# PocketBeagle.net
KiCad netlist of a schematic drawn in EAGLE
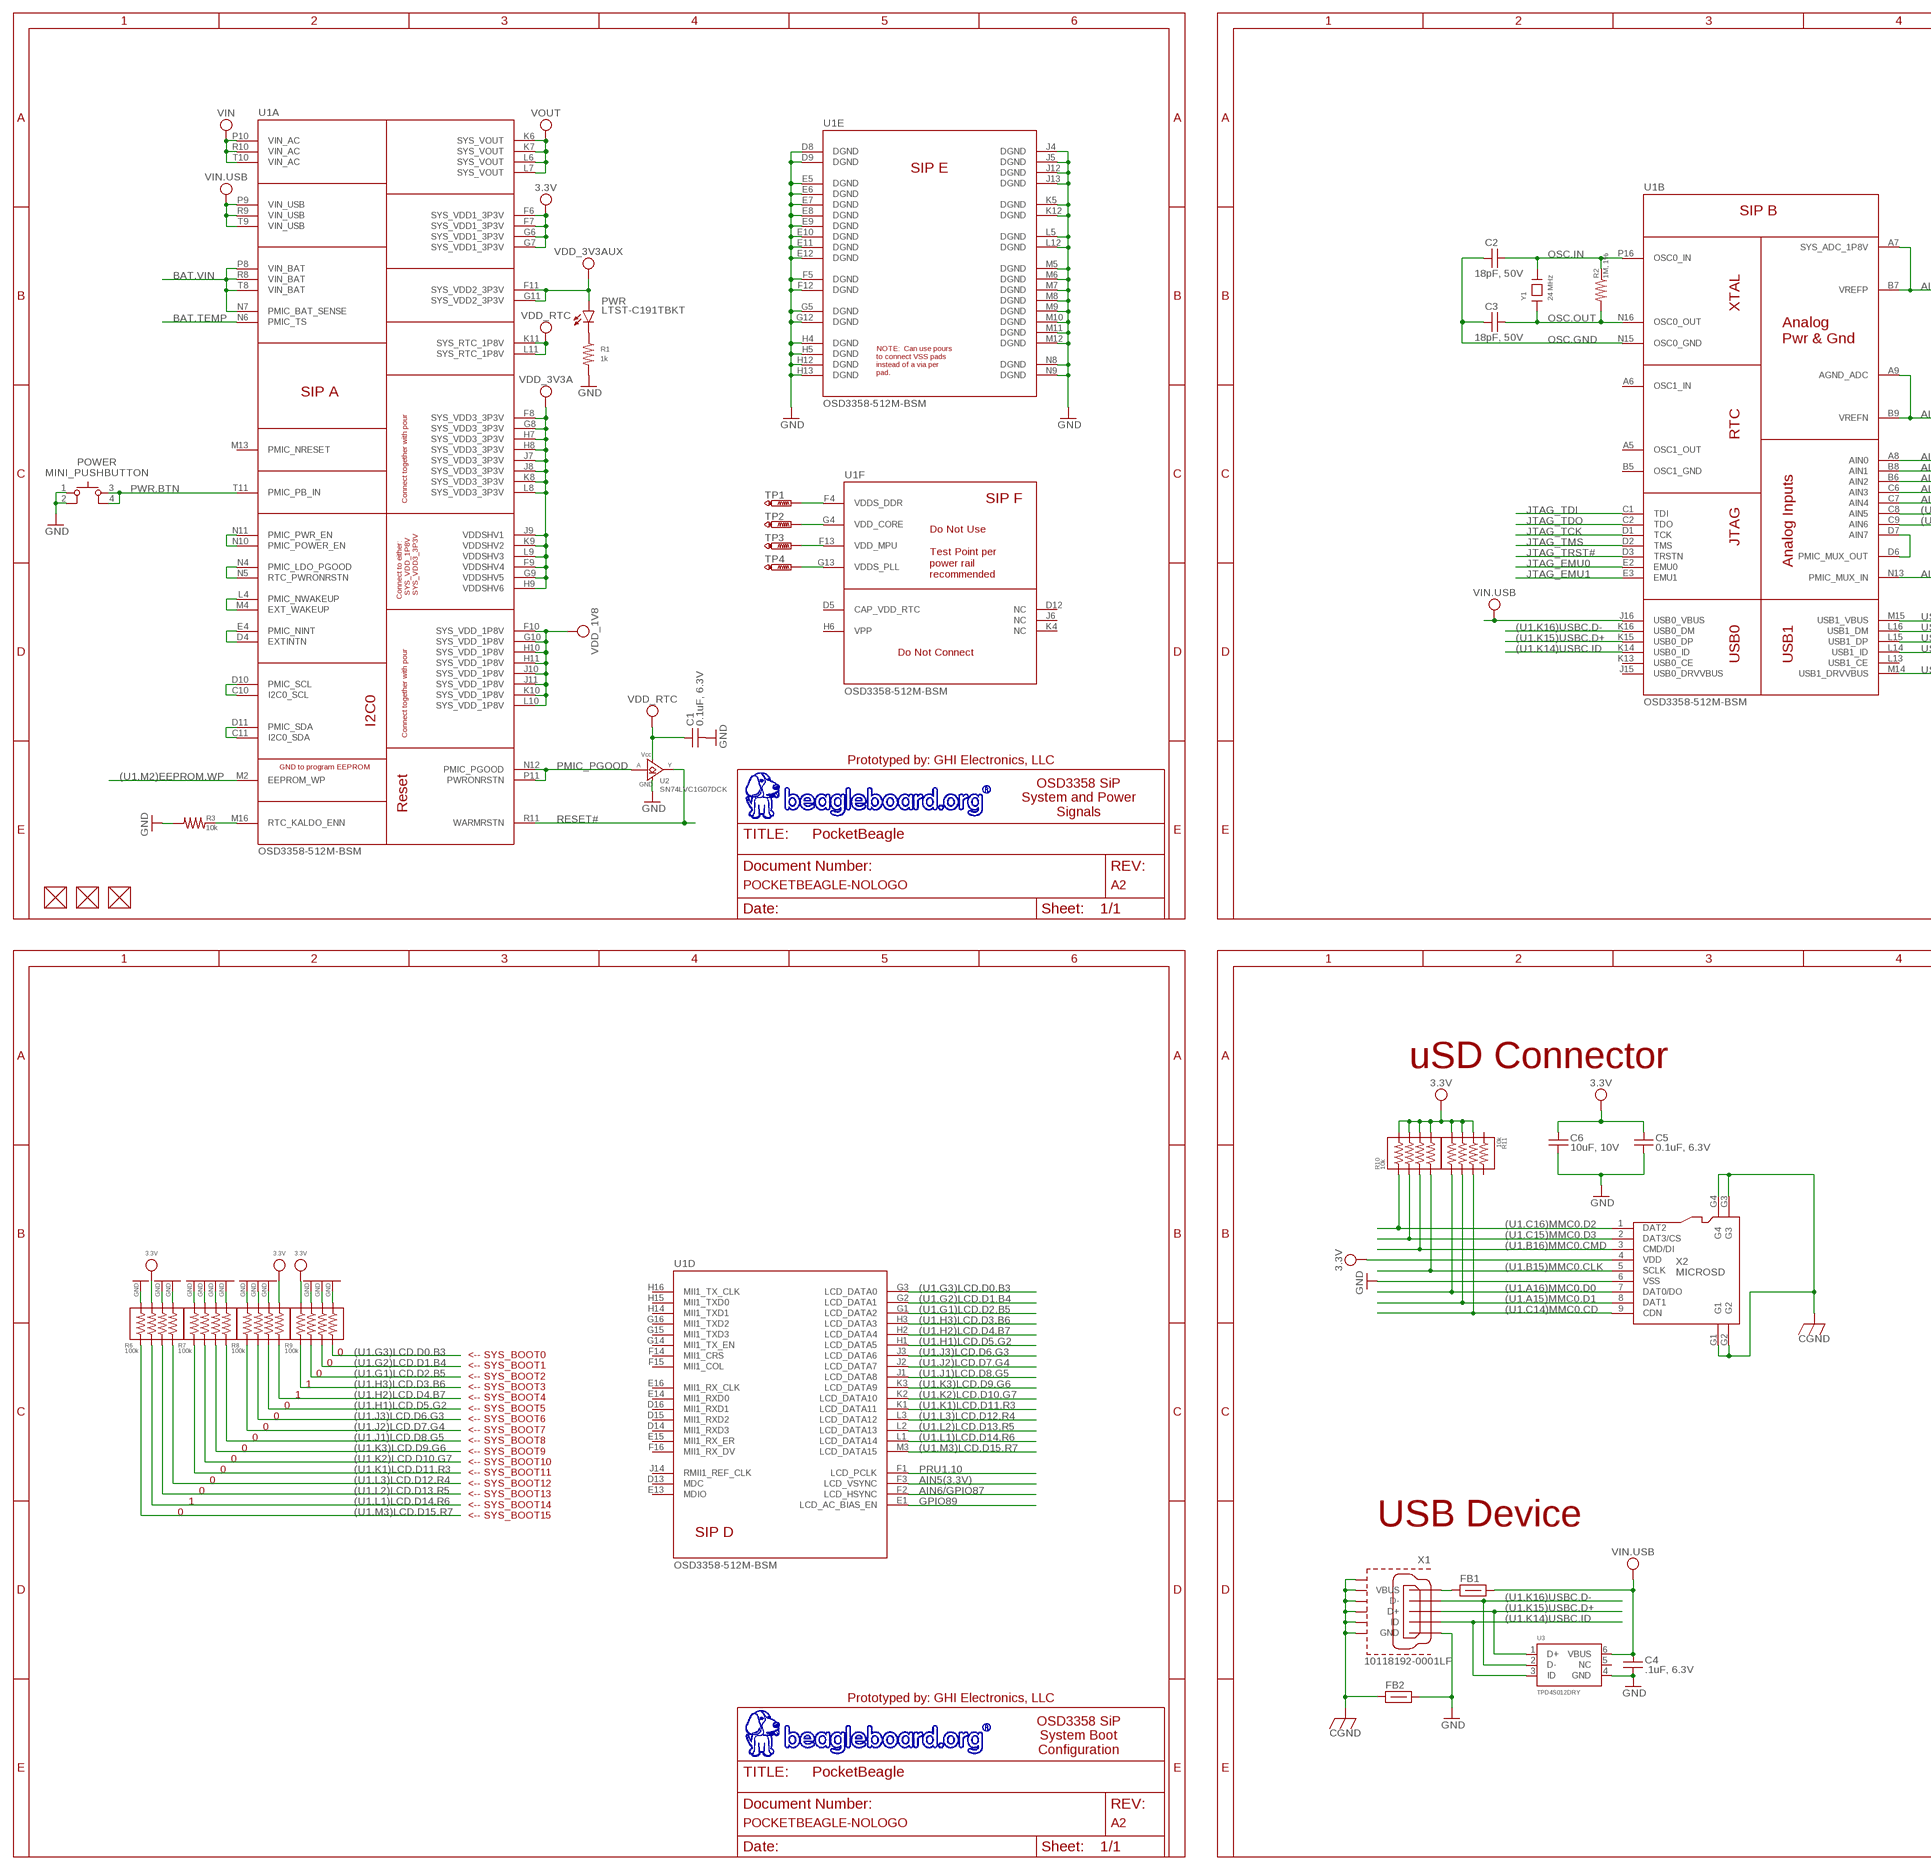
[diagram p0: schematic, sheet 1, part 1 of 2]
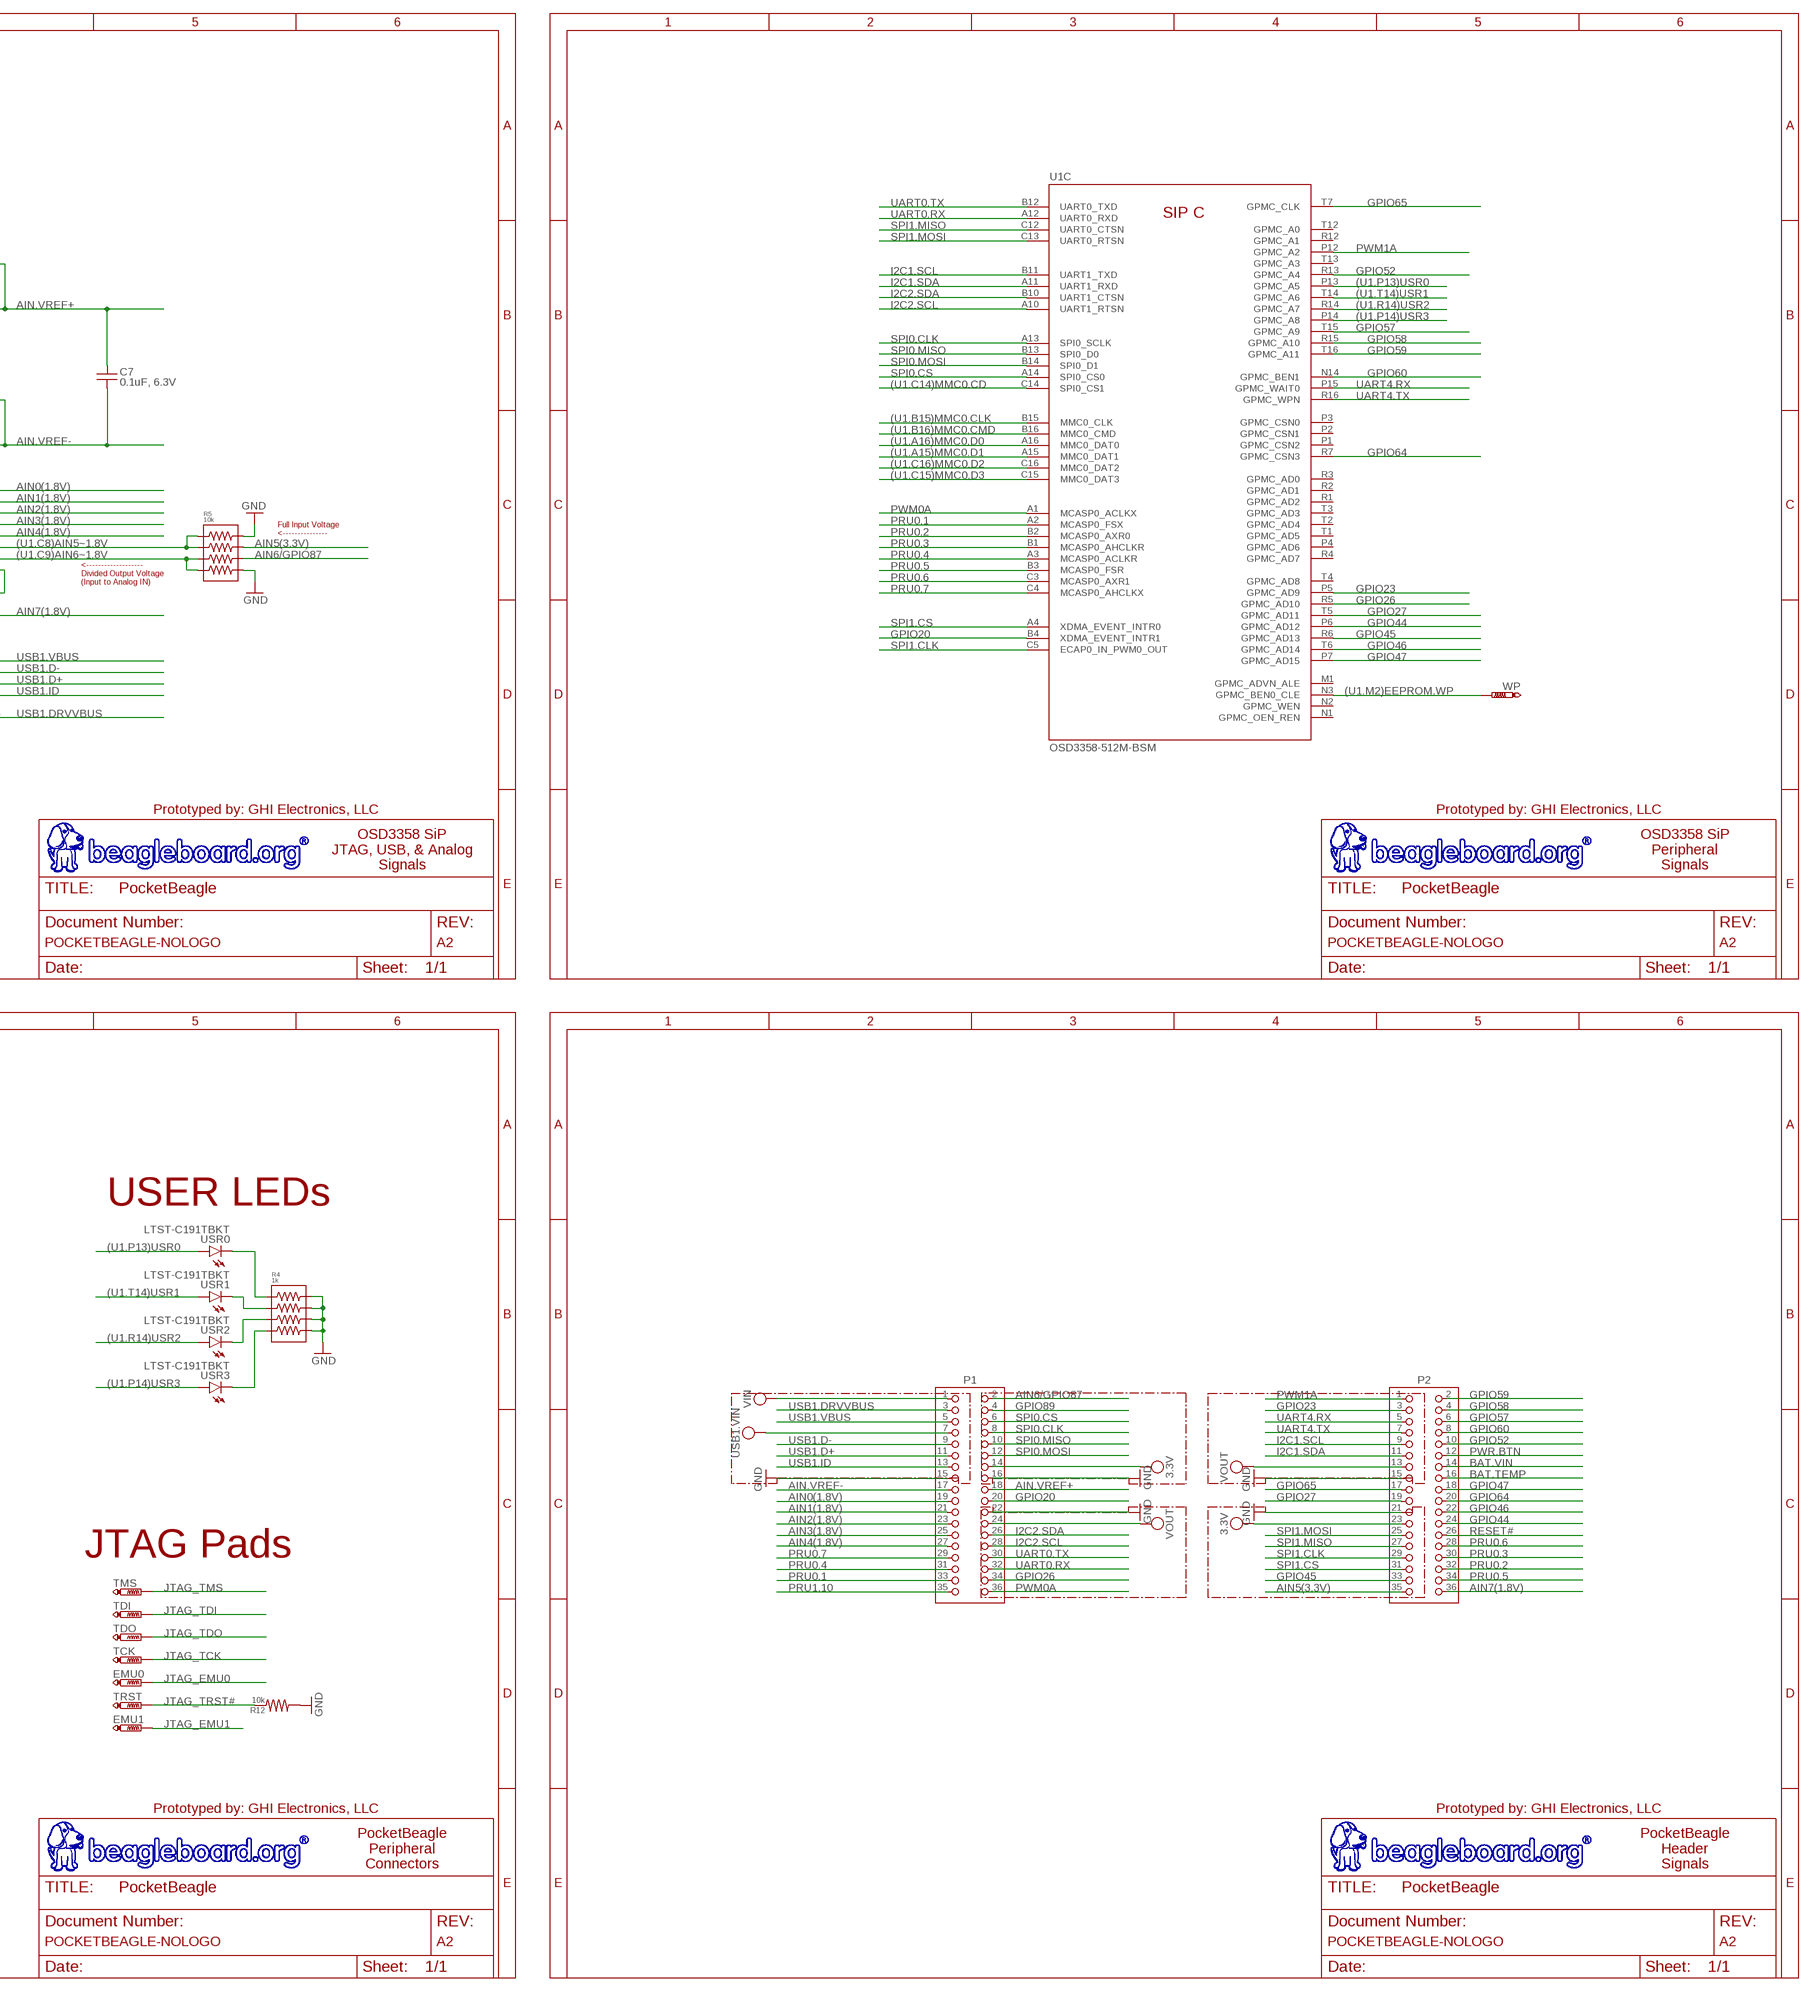
[diagram p1: schematic, sheet 1, part 2 of 2]

(export (version "E")
  (design (tool "Eeschema 10.0.6"))
  (components
    (comp (ref "C1")
      (value "0.1uF, 6.3V")
      (footprint "eagle-import:0402")
      (libsource (lib "eagle-import") (part "CAPACITOR-(INCH)-0402"))
    )
    (comp (ref "C2")
      (value "18pF, 50V")
      (footprint "eagle-import:0402")
      (libsource (lib "eagle-import") (part "CAPACITOR-(INCH)-0402"))
    )
    (comp (ref "C3")
      (value "18pF, 50V")
      (footprint "eagle-import:0402")
      (libsource (lib "eagle-import") (part "CAPACITOR-(INCH)-0402"))
    )
    (comp (ref "C4")
      (value ".1uF, 6.3V")
      (footprint "eagle-import:0402")
      (libsource (lib "eagle-import") (part "CAPACITOR-(INCH)-0402"))
    )
    (comp (ref "C5")
      (value "0.1uF, 6.3V")
      (footprint "eagle-import:0402")
      (libsource (lib "eagle-import") (part "CAPACITOR-(INCH)-0402"))
    )
    (comp (ref "C6")
      (value "10uF, 10V")
      (footprint "eagle-import:0603")
      (libsource (lib "eagle-import") (part "CAPACITOR-(INCH)-0603"))
    )
    (comp (ref "C7")
      (value "0.1uF, 6.3V")
      (footprint "eagle-import:0402")
      (libsource (lib "eagle-import") (part "CAPACITOR-(INCH)-0402"))
    )
    (comp (ref "EMU0")
      (value "PTR1B1,27")
      (footprint "eagle-import:B1,27")
      (libsource (lib "eagle-import") (part "PTR1B1,27"))
    )
    (comp (ref "EMU1")
      (value "PTR1B1,27")
      (footprint "eagle-import:B1,27")
      (libsource (lib "eagle-import") (part "PTR1B1,27"))
    )
    (comp (ref "FB1")
      (value "FB-(INCH)-0603")
      (footprint "eagle-import:0603")
      (libsource (lib "eagle-import") (part "FB-(INCH)-0603"))
    )
    (comp (ref "FB2")
      (value "FB-(INCH)-0603")
      (footprint "eagle-import:0603")
      (libsource (lib "eagle-import") (part "FB-(INCH)-0603"))
    )
    (comp (ref "FUD1")
      (value "FIDUCIAL")
      (footprint "eagle-import:FIDUCIAL_40MIL")
      (libsource (lib "eagle-import") (part "FIDUCIAL"))
    )
    (comp (ref "FUD2")
      (value "FIDUCIAL")
      (footprint "eagle-import:FIDUCIAL_40MIL")
      (libsource (lib "eagle-import") (part "FIDUCIAL"))
    )
    (comp (ref "FUD3")
      (value "FIDUCIAL")
      (footprint "eagle-import:FIDUCIAL_40MIL")
      (libsource (lib "eagle-import") (part "FIDUCIAL"))
    )
    (comp (ref "P1")
      (value "2X18-(INCH)-0.1-TH-(35MIL-DIA)-W/O-SILK")
      (footprint "eagle-import:TH-2X18-(35MIL-DIA)-W_O-SILK")
      (libsource (lib "eagle-import") (part "2X18-(INCH)-0.1-TH-(35MIL-DIA)-W/O-SILK"))
    )
    (comp (ref "P2")
      (value "2X18-(INCH)-0.1-TH-(35MIL-DIA)-W/O-SILK")
      (footprint "eagle-import:TH-2X18-(35MIL-DIA)-W_O-SILK")
      (libsource (lib "eagle-import") (part "2X18-(INCH)-0.1-TH-(35MIL-DIA)-W/O-SILK"))
    )
    (comp (ref "POWER")
      (value "MINI_PUSHBUTTON")
      (footprint "eagle-import:MINI_PUSHBUTTON")
      (libsource (lib "eagle-import") (part "MINI_PUSHBUTTON"))
    )
    (comp (ref "PWR")
      (value "LTST-C191TBKT")
      (footprint "eagle-import:0603-LED")
      (libsource (lib "eagle-import") (part "LED-(INCH)-0603"))
    )
    (comp (ref "R1")
      (value "1k")
      (footprint "eagle-import:0402")
      (libsource (lib "eagle-import") (part "RESISTOR-(INCH)-0402"))
    )
    (comp (ref "R2")
      (value "1M, 1%")
      (footprint "eagle-import:0402")
      (libsource (lib "eagle-import") (part "RESISTOR-(INCH)-0402"))
    )
    (comp (ref "R3")
      (value "10k")
      (footprint "eagle-import:0402")
      (libsource (lib "eagle-import") (part "RESISTOR-(INCH)-0402"))
    )
    (comp (ref "R4")
      (value "1k")
      (footprint "eagle-import:RN0804")
      (libsource (lib "eagle-import") (part "RESISTOR.NETWORK-(4)"))
    )
    (comp (ref "R5")
      (value "10k")
      (footprint "eagle-import:RN0804")
      (libsource (lib "eagle-import") (part "RESISTOR.NETWORK-(4)"))
    )
    (comp (ref "R6")
      (value "100k")
      (footprint "eagle-import:RN0804")
      (libsource (lib "eagle-import") (part "RESISTOR.NETWORK-(4)"))
    )
    (comp (ref "R7")
      (value "100k")
      (footprint "eagle-import:RN0804")
      (libsource (lib "eagle-import") (part "RESISTOR.NETWORK-(4)"))
    )
    (comp (ref "R8")
      (value "100k")
      (footprint "eagle-import:RN0804")
      (libsource (lib "eagle-import") (part "RESISTOR.NETWORK-(4)"))
    )
    (comp (ref "R9")
      (value "100k")
      (footprint "eagle-import:RN0804")
      (libsource (lib "eagle-import") (part "RESISTOR.NETWORK-(4)"))
    )
    (comp (ref "R10")
      (value "10k")
      (footprint "eagle-import:RN0804")
      (libsource (lib "eagle-import") (part "RESISTOR.NETWORK-(4)"))
    )
    (comp (ref "R11")
      (value "10k")
      (footprint "eagle-import:RN0804")
      (libsource (lib "eagle-import") (part "RESISTOR.NETWORK-(4)"))
    )
    (comp (ref "R12")
      (value "10k")
      (footprint "eagle-import:0402")
      (libsource (lib "eagle-import") (part "RESISTOR-(INCH)-0402"))
    )
    (comp (ref "TCK")
      (value "PTR1B1,27")
      (footprint "eagle-import:B1,27")
      (libsource (lib "eagle-import") (part "PTR1B1,27"))
    )
    (comp (ref "TDI")
      (value "PTR1B1,27")
      (footprint "eagle-import:B1,27")
      (libsource (lib "eagle-import") (part "PTR1B1,27"))
    )
    (comp (ref "TDO")
      (value "PTR1B1,27")
      (footprint "eagle-import:B1,27")
      (libsource (lib "eagle-import") (part "PTR1B1,27"))
    )
    (comp (ref "TMS")
      (value "PTR1B1,27")
      (footprint "eagle-import:B1,27")
      (libsource (lib "eagle-import") (part "PTR1B1,27"))
    )
    (comp (ref "TP1")
      (value "PTR1B1,27")
      (footprint "eagle-import:B1,27")
      (libsource (lib "eagle-import") (part "PTR1B1,27"))
    )
    (comp (ref "TP2")
      (value "PTR1B1,27")
      (footprint "eagle-import:B1,27")
      (libsource (lib "eagle-import") (part "PTR1B1,27"))
    )
    (comp (ref "TP3")
      (value "PTR1B1,27")
      (footprint "eagle-import:B1,27")
      (libsource (lib "eagle-import") (part "PTR1B1,27"))
    )
    (comp (ref "TP4")
      (value "PTR1B1,27")
      (footprint "eagle-import:B1,27")
      (libsource (lib "eagle-import") (part "PTR1B1,27"))
    )
    (comp (ref "TRST")
      (value "PTR1B1,27")
      (footprint "eagle-import:B1,27")
      (libsource (lib "eagle-import") (part "PTR1B1,27"))
    )
    (comp (ref "U1")
      (value "OSD3358-512M-BSM")
      (footprint "eagle-import:OSD335X-BGA-256")
      (libsource (lib "eagle-import") (part "OSD3358-512M-BSM"))
    )
    (comp (ref "U2")
      (value "SN74LVC1G07DCK")
      (footprint "eagle-import:SC70(TI-DCK)")
      (libsource (lib "eagle-import") (part "SN74LVC1G07DCK"))
    )
    (comp (ref "U3")
      (value "TPD4S012DRY")
      (footprint "eagle-import:SON-6(TI)-DRY")
      (libsource (lib "eagle-import") (part "TPD4S012DRYR"))
    )
    (comp (ref "USR0")
      (value "LTST-C191TBKT")
      (footprint "eagle-import:0603-LED")
      (libsource (lib "eagle-import") (part "LED-(INCH)-0603"))
    )
    (comp (ref "USR1")
      (value "LTST-C191TBKT")
      (footprint "eagle-import:0603-LED")
      (libsource (lib "eagle-import") (part "LED-(INCH)-0603"))
    )
    (comp (ref "USR2")
      (value "LTST-C191TBKT")
      (footprint "eagle-import:0603-LED")
      (libsource (lib "eagle-import") (part "LED-(INCH)-0603"))
    )
    (comp (ref "USR3")
      (value "LTST-C191TBKT")
      (footprint "eagle-import:0603-LED")
      (libsource (lib "eagle-import") (part "LED-(INCH)-0603"))
    )
    (comp (ref "WP")
      (value "PTR1B1,27")
      (footprint "eagle-import:B1,27")
      (libsource (lib "eagle-import") (part "PTR1B1,27"))
    )
    (comp (ref "X1")
      (value "10118192-0001LF")
      (footprint "eagle-import:10118192-0001LF(MICRO-USB-B-AMPHENOL-FCI)")
      (libsource (lib "eagle-import") (part "10118192-0001LF"))
    )
    (comp (ref "X2")
      (value "MICROSD")
      (footprint "eagle-import:MICROSD")
      (libsource (lib "eagle-import") (part "MICROSD"))
    )
    (comp (ref "Y1")
      (value "24 MHz")
      (footprint "eagle-import:CRYSTAL_5X3.2MM")
      (libsource (lib "eagle-import") (part "CRYSTAL_5X3.2MM"))
    )
  )
  (nets
    (net (code "1") (name "/(U1.A15)MMC0.D1") (class "Default")
      (node (ref "R11") (pin "6") (pinfunction "6_6") (pintype "bidirectional"))
      (node (ref "U1") (pin "A15") (pinfunction "MMC0_DAT1_A15") (pintype "bidirectional"))
      (node (ref "X2") (pin "8") (pinfunction "DAT1_8") (pintype "bidirectional"))
    )
    (net (code "2") (name "/(U1.A16)MMC0.D0") (class "Default")
      (node (ref "R11") (pin "5") (pinfunction "5_5") (pintype "bidirectional"))
      (node (ref "U1") (pin "A16") (pinfunction "MMC0_DAT0_A16") (pintype "bidirectional"))
      (node (ref "X2") (pin "7") (pinfunction "DAT0/DO_7") (pintype "bidirectional"))
    )
    (net (code "3") (name "/(U1.B15)MMC0.CLK") (class "Default")
      (node (ref "R10") (pin "4") (pinfunction "4_4") (pintype "bidirectional"))
      (node (ref "U1") (pin "B15") (pinfunction "MMC0_CLK_B15") (pintype "bidirectional"))
      (node (ref "X2") (pin "5") (pinfunction "SCLK_5") (pintype "bidirectional"))
    )
    (net (code "4") (name "/(U1.B16)MMC0.CMD") (class "Default")
      (node (ref "R10") (pin "3") (pinfunction "3_3") (pintype "bidirectional"))
      (node (ref "U1") (pin "B16") (pinfunction "MMC0_CMD_B16") (pintype "bidirectional"))
      (node (ref "X2") (pin "3") (pinfunction "CMD/DI_3") (pintype "bidirectional"))
    )
    (net (code "5") (name "/(U1.C8)AIN5~{1.8V}") (class "Default")
      (node (ref "R5") (pin "1") (pinfunction "1_1") (pintype "bidirectional"))
      (node (ref "R5") (pin "2") (pinfunction "2_2") (pintype "bidirectional"))
      (node (ref "U1") (pin "C8") (pinfunction "AIN5_C8") (pintype "bidirectional"))
    )
    (net (code "6") (name "/(U1.C9)AIN6~{1.8V}") (class "Default")
      (node (ref "R5") (pin "3") (pinfunction "3_3") (pintype "bidirectional"))
      (node (ref "R5") (pin "4") (pinfunction "4_4") (pintype "bidirectional"))
      (node (ref "U1") (pin "C9") (pinfunction "AIN6_C9") (pintype "bidirectional"))
    )
    (net (code "7") (name "/(U1.C14)MMC0.CD") (class "Default")
      (node (ref "R11") (pin "7") (pinfunction "7_7") (pintype "bidirectional"))
      (node (ref "U1") (pin "C14") (pinfunction "SPI0_CS1_C14") (pintype "bidirectional"))
      (node (ref "X2") (pin "9") (pinfunction "CDN_9") (pintype "bidirectional"))
    )
    (net (code "8") (name "/(U1.C15)MMC0.D3") (class "Default")
      (node (ref "R10") (pin "2") (pinfunction "2_2") (pintype "bidirectional"))
      (node (ref "U1") (pin "C15") (pinfunction "MMC0_DAT3_C15") (pintype "bidirectional"))
      (node (ref "X2") (pin "2") (pinfunction "DAT3/CS_2") (pintype "bidirectional"))
    )
    (net (code "9") (name "/(U1.C16)MMC0.D2") (class "Default")
      (node (ref "R10") (pin "1") (pinfunction "1_1") (pintype "bidirectional"))
      (node (ref "U1") (pin "C16") (pinfunction "MMC0_DAT2_C16") (pintype "bidirectional"))
      (node (ref "X2") (pin "1") (pinfunction "DAT2_1") (pintype "bidirectional"))
    )
    (net (code "10") (name "/(U1.G1)LCD.D2.B5") (class "Default")
      (node (ref "R9") (pin "6") (pinfunction "6_6") (pintype "bidirectional"))
      (node (ref "U1") (pin "G1") (pinfunction "LCD_DATA2_G1") (pintype "bidirectional"))
    )
    (net (code "11") (name "/(U1.G2)LCD.D1.B4") (class "Default")
      (node (ref "R9") (pin "7") (pinfunction "7_7") (pintype "bidirectional"))
      (node (ref "U1") (pin "G2") (pinfunction "LCD_DATA1_G2") (pintype "bidirectional"))
    )
    (net (code "12") (name "/(U1.G3)LCD.D0.B3") (class "Default")
      (node (ref "R9") (pin "8") (pinfunction "8_8") (pintype "bidirectional"))
      (node (ref "U1") (pin "G3") (pinfunction "LCD_DATA0_G3") (pintype "bidirectional"))
    )
    (net (code "13") (name "/(U1.H1)LCD.D5.G2") (class "Default")
      (node (ref "R8") (pin "3") (pinfunction "3_3") (pintype "bidirectional"))
      (node (ref "U1") (pin "H1") (pinfunction "LCD_DATA5_H1") (pintype "bidirectional"))
    )
    (net (code "14") (name "/(U1.H2)LCD.D4.B7") (class "Default")
      (node (ref "R8") (pin "4") (pinfunction "4_4") (pintype "bidirectional"))
      (node (ref "U1") (pin "H2") (pinfunction "LCD_DATA4_H2") (pintype "bidirectional"))
    )
    (net (code "15") (name "/(U1.H3)LCD.D3.B6") (class "Default")
      (node (ref "R9") (pin "5") (pinfunction "5_5") (pintype "bidirectional"))
      (node (ref "U1") (pin "H3") (pinfunction "LCD_DATA3_H3") (pintype "bidirectional"))
    )
    (net (code "16") (name "/(U1.J1)LCD.D8.G5") (class "Default")
      (node (ref "R7") (pin "4") (pinfunction "4_4") (pintype "bidirectional"))
      (node (ref "U1") (pin "J1") (pinfunction "LCD_DATA8_J1") (pintype "bidirectional"))
    )
    (net (code "17") (name "/(U1.J2)LCD.D7.G4") (class "Default")
      (node (ref "R8") (pin "1") (pinfunction "1_1") (pintype "bidirectional"))
      (node (ref "U1") (pin "J2") (pinfunction "LCD_DATA7_J2") (pintype "bidirectional"))
    )
    (net (code "18") (name "/(U1.J3)LCD.D6.G3") (class "Default")
      (node (ref "R8") (pin "2") (pinfunction "2_2") (pintype "bidirectional"))
      (node (ref "U1") (pin "J3") (pinfunction "LCD_DATA6_J3") (pintype "bidirectional"))
    )
    (net (code "19") (name "/(U1.K1)LCD.D11.R3") (class "Default")
      (node (ref "R7") (pin "1") (pinfunction "1_1") (pintype "bidirectional"))
      (node (ref "U1") (pin "K1") (pinfunction "LCD_DATA11_K1") (pintype "bidirectional"))
    )
    (net (code "20") (name "/(U1.K2)LCD.D10.G7") (class "Default")
      (node (ref "R7") (pin "2") (pinfunction "2_2") (pintype "bidirectional"))
      (node (ref "U1") (pin "K2") (pinfunction "LCD_DATA10_K2") (pintype "bidirectional"))
    )
    (net (code "21") (name "/(U1.K3)LCD.D9.G6") (class "Default")
      (node (ref "R7") (pin "3") (pinfunction "3_3") (pintype "bidirectional"))
      (node (ref "U1") (pin "K3") (pinfunction "LCD_DATA9_K3") (pintype "bidirectional"))
    )
    (net (code "22") (name "/(U1.K14)USBC.ID") (class "Default")
      (node (ref "U1") (pin "K14") (pinfunction "USB0_ID_K14") (pintype "bidirectional"))
      (node (ref "U3") (pin "3") (pinfunction "ID_3") (pintype "bidirectional"))
      (node (ref "X1") (pin "ID") (pinfunction "ID_ID") (pintype "input"))
    )
    (net (code "23") (name "/(U1.K15)USBC.D+") (class "Default")
      (node (ref "U1") (pin "K15") (pinfunction "USB0_DP_K15") (pintype "bidirectional"))
      (node (ref "U3") (pin "1") (pinfunction "D+_1") (pintype "bidirectional"))
      (node (ref "X1") (pin "D+") (pinfunction "D+_D+") (pintype "input"))
    )
    (net (code "24") (name "/(U1.K16)USBC.D-") (class "Default")
      (node (ref "U1") (pin "K16") (pinfunction "USB0_DM_K16") (pintype "bidirectional"))
      (node (ref "U3") (pin "2") (pinfunction "D-_2") (pintype "bidirectional"))
      (node (ref "X1") (pin "D-") (pinfunction "D-_D-") (pintype "input"))
    )
    (net (code "25") (name "/(U1.L1)LCD.D14.R6") (class "Default")
      (node (ref "R6") (pin "2") (pinfunction "2_2") (pintype "bidirectional"))
      (node (ref "U1") (pin "L1") (pinfunction "LCD_DATA14_L1") (pintype "bidirectional"))
    )
    (net (code "26") (name "/(U1.L2)LCD.D13.R5") (class "Default")
      (node (ref "R6") (pin "3") (pinfunction "3_3") (pintype "bidirectional"))
      (node (ref "U1") (pin "L2") (pinfunction "LCD_DATA13_L2") (pintype "bidirectional"))
    )
    (net (code "27") (name "/(U1.L3)LCD.D12.R4") (class "Default")
      (node (ref "R6") (pin "4") (pinfunction "4_4") (pintype "bidirectional"))
      (node (ref "U1") (pin "L3") (pinfunction "LCD_DATA12_L3") (pintype "bidirectional"))
    )
    (net (code "28") (name "/(U1.M2)EEPROM.WP") (class "Default")
      (node (ref "U1") (pin "M2") (pinfunction "EEPROM_WP_M2") (pintype "bidirectional"))
      (node (ref "U1") (pin "N3") (pinfunction "GPMC_BEN0_CLE_N3") (pintype "bidirectional"))
      (node (ref "WP") (pin "TP") (pinfunction "TP_TP") (pintype "input"))
    )
    (net (code "29") (name "/(U1.M3)LCD.D15.R7") (class "Default")
      (node (ref "R6") (pin "1") (pinfunction "1_1") (pintype "bidirectional"))
      (node (ref "U1") (pin "M3") (pinfunction "LCD_DATA15_M3") (pintype "bidirectional"))
    )
    (net (code "30") (name "/(U1.P13)USR0") (class "Default")
      (node (ref "U1") (pin "P13") (pinfunction "GPMC_A5_P13") (pintype "bidirectional"))
      (node (ref "USR0") (pin "A") (pinfunction "A_A") (pintype "passive"))
    )
    (net (code "31") (name "/(U1.P14)USR3") (class "Default")
      (node (ref "U1") (pin "P14") (pinfunction "GPMC_A8_P14") (pintype "bidirectional"))
      (node (ref "USR3") (pin "A") (pinfunction "A_A") (pintype "passive"))
    )
    (net (code "32") (name "/(U1.R14)USR2") (class "Default")
      (node (ref "U1") (pin "R14") (pinfunction "GPMC_A7_R14") (pintype "bidirectional"))
      (node (ref "USR2") (pin "A") (pinfunction "A_A") (pintype "passive"))
    )
    (net (code "33") (name "/(U1.T14)USR1") (class "Default")
      (node (ref "U1") (pin "T14") (pinfunction "GPMC_A6_T14") (pintype "bidirectional"))
      (node (ref "USR1") (pin "A") (pinfunction "A_A") (pintype "passive"))
    )
    (net (code "34") (name "/AIN.VREF+") (class "Default")
      (node (ref "C7") (pin "1") (pinfunction "1_1") (pintype "bidirectional"))
      (node (ref "P1") (pin "18") (pinfunction "18_18") (pintype "bidirectional"))
      (node (ref "U1") (pin "A7") (pinfunction "SYS_ADC_1P8V_A7") (pintype "bidirectional"))
      (node (ref "U1") (pin "B7") (pinfunction "VREFP_B7") (pintype "bidirectional"))
    )
    (net (code "35") (name "/AIN.VREF-") (class "Default")
      (node (ref "C7") (pin "2") (pinfunction "2_2") (pintype "bidirectional"))
      (node (ref "P1") (pin "17") (pinfunction "17_17") (pintype "bidirectional"))
      (node (ref "U1") (pin "A9") (pinfunction "AGND_ADC_A9") (pintype "bidirectional"))
      (node (ref "U1") (pin "B9") (pinfunction "VREFN_B9") (pintype "bidirectional"))
    )
    (net (code "36") (name "/AIN0(1.8V)") (class "Default")
      (node (ref "P1") (pin "19") (pinfunction "19_19") (pintype "bidirectional"))
      (node (ref "U1") (pin "A8") (pinfunction "AIN0_A8") (pintype "bidirectional"))
    )
    (net (code "37") (name "/AIN1(1.8V)") (class "Default")
      (node (ref "P1") (pin "21") (pinfunction "21_21") (pintype "bidirectional"))
      (node (ref "U1") (pin "B8") (pinfunction "AIN1_B8") (pintype "bidirectional"))
    )
    (net (code "38") (name "/AIN2(1.8V)") (class "Default")
      (node (ref "P1") (pin "23") (pinfunction "23_23") (pintype "bidirectional"))
      (node (ref "U1") (pin "B6") (pinfunction "AIN2_B6") (pintype "bidirectional"))
    )
    (net (code "39") (name "/AIN3(1.8V)") (class "Default")
      (node (ref "P1") (pin "25") (pinfunction "25_25") (pintype "bidirectional"))
      (node (ref "U1") (pin "C6") (pinfunction "AIN3_C6") (pintype "bidirectional"))
    )
    (net (code "40") (name "/AIN4(1.8V)") (class "Default")
      (node (ref "P1") (pin "27") (pinfunction "27_27") (pintype "bidirectional"))
      (node (ref "U1") (pin "C7") (pinfunction "AIN4_C7") (pintype "bidirectional"))
    )
    (net (code "41") (name "/AIN5(3.3V)") (class "Default")
      (node (ref "P2") (pin "35") (pinfunction "35_35") (pintype "bidirectional"))
      (node (ref "R5") (pin "7") (pinfunction "7_7") (pintype "bidirectional"))
      (node (ref "U1") (pin "F3") (pinfunction "LCD_VSYNC_F3") (pintype "bidirectional"))
    )
    (net (code "42") (name "/AIN6{slash}GPIO87") (class "Default")
      (node (ref "P1") (pin "2") (pinfunction "2_2") (pintype "bidirectional"))
      (node (ref "R5") (pin "6") (pinfunction "6_6") (pintype "bidirectional"))
      (node (ref "U1") (pin "F2") (pinfunction "LCD_HSYNC_F2") (pintype "bidirectional"))
    )
    (net (code "43") (name "/AIN7(1.8V)") (class "Default")
      (node (ref "P2") (pin "36") (pinfunction "36_36") (pintype "bidirectional"))
      (node (ref "U1") (pin "N13") (pinfunction "PMIC_MUX_IN_N13") (pintype "bidirectional"))
    )
    (net (code "44") (name "/BAT.TEMP") (class "Default")
      (node (ref "P2") (pin "16") (pinfunction "16_16") (pintype "bidirectional"))
      (node (ref "U1") (pin "N6") (pinfunction "PMIC_TS_N6") (pintype "bidirectional"))
    )
    (net (code "45") (name "/BAT.VIN") (class "Default")
      (node (ref "P2") (pin "14") (pinfunction "14_14") (pintype "bidirectional"))
      (node (ref "U1") (pin "N7") (pinfunction "PMIC_BAT_SENSE_N7") (pintype "bidirectional"))
      (node (ref "U1") (pin "P8") (pinfunction "VIN_BAT_P8") (pintype "power_in"))
      (node (ref "U1") (pin "R8") (pinfunction "VIN_BAT_R8") (pintype "power_in"))
      (node (ref "U1") (pin "T8") (pinfunction "VIN_BAT_T8") (pintype "power_in"))
    )
    (net (code "46") (name "/GPIO20") (class "Default")
      (node (ref "P1") (pin "20") (pinfunction "20_20") (pintype "bidirectional"))
      (node (ref "U1") (pin "B4") (pinfunction "XDMA_EVENT_INTR1_B4") (pintype "bidirectional"))
    )
    (net (code "47") (name "/GPIO23") (class "Default")
      (node (ref "P2") (pin "3") (pinfunction "3_3") (pintype "bidirectional"))
      (node (ref "U1") (pin "P5") (pinfunction "GPMC_AD9_P5") (pintype "bidirectional"))
    )
    (net (code "48") (name "/GPIO26") (class "Default")
      (node (ref "P1") (pin "34") (pinfunction "34_34") (pintype "bidirectional"))
      (node (ref "U1") (pin "R5") (pinfunction "GPMC_AD10_R5") (pintype "bidirectional"))
    )
    (net (code "49") (name "/GPIO27") (class "Default")
      (node (ref "P2") (pin "19") (pinfunction "19_19") (pintype "bidirectional"))
      (node (ref "U1") (pin "T5") (pinfunction "GPMC_AD11_T5") (pintype "bidirectional"))
    )
    (net (code "50") (name "/GPIO44") (class "Default")
      (node (ref "P2") (pin "24") (pinfunction "24_24") (pintype "bidirectional"))
      (node (ref "U1") (pin "P6") (pinfunction "GPMC_AD12_P6") (pintype "bidirectional"))
    )
    (net (code "51") (name "/GPIO45") (class "Default")
      (node (ref "P2") (pin "33") (pinfunction "33_33") (pintype "bidirectional"))
      (node (ref "U1") (pin "R6") (pinfunction "GPMC_AD13_R6") (pintype "bidirectional"))
    )
    (net (code "52") (name "/GPIO46") (class "Default")
      (node (ref "P2") (pin "22") (pinfunction "22_22") (pintype "bidirectional"))
      (node (ref "U1") (pin "T6") (pinfunction "GPMC_AD14_T6") (pintype "bidirectional"))
    )
    (net (code "53") (name "/GPIO47") (class "Default")
      (node (ref "P2") (pin "18") (pinfunction "18_18") (pintype "bidirectional"))
      (node (ref "U1") (pin "P7") (pinfunction "GPMC_AD15_P7") (pintype "bidirectional"))
    )
    (net (code "54") (name "/GPIO52") (class "Default")
      (node (ref "P2") (pin "10") (pinfunction "10_10") (pintype "bidirectional"))
      (node (ref "U1") (pin "R13") (pinfunction "GPMC_A4_R13") (pintype "bidirectional"))
    )
    (net (code "55") (name "/GPIO57") (class "Default")
      (node (ref "P2") (pin "6") (pinfunction "6_6") (pintype "bidirectional"))
      (node (ref "U1") (pin "T15") (pinfunction "GPMC_A9_T15") (pintype "bidirectional"))
    )
    (net (code "56") (name "/GPIO58") (class "Default")
      (node (ref "P2") (pin "4") (pinfunction "4_4") (pintype "bidirectional"))
      (node (ref "U1") (pin "R15") (pinfunction "GPMC_A10_R15") (pintype "bidirectional"))
    )
    (net (code "57") (name "/GPIO59") (class "Default")
      (node (ref "P2") (pin "2") (pinfunction "2_2") (pintype "bidirectional"))
      (node (ref "U1") (pin "T16") (pinfunction "GPMC_A11_T16") (pintype "bidirectional"))
    )
    (net (code "58") (name "/GPIO60") (class "Default")
      (node (ref "P2") (pin "8") (pinfunction "8_8") (pintype "bidirectional"))
      (node (ref "U1") (pin "N14") (pinfunction "GPMC_BEN1_N14") (pintype "bidirectional"))
    )
    (net (code "59") (name "/GPIO64") (class "Default")
      (node (ref "P2") (pin "20") (pinfunction "20_20") (pintype "bidirectional"))
      (node (ref "U1") (pin "R7") (pinfunction "GPMC_CSN3_R7") (pintype "bidirectional"))
    )
    (net (code "60") (name "/GPIO65") (class "Default")
      (node (ref "P2") (pin "17") (pinfunction "17_17") (pintype "bidirectional"))
      (node (ref "U1") (pin "T7") (pinfunction "GPMC_CLK_T7") (pintype "bidirectional"))
    )
    (net (code "61") (name "/GPIO89") (class "Default")
      (node (ref "P1") (pin "4") (pinfunction "4_4") (pintype "bidirectional"))
      (node (ref "U1") (pin "E1") (pinfunction "LCD_AC_BIAS_EN_E1") (pintype "bidirectional"))
    )
    (net (code "62") (name "/I2C1.SCL") (class "Default")
      (node (ref "P2") (pin "9") (pinfunction "9_9") (pintype "bidirectional"))
      (node (ref "U1") (pin "B11") (pinfunction "UART1_TXD_B11") (pintype "bidirectional"))
    )
    (net (code "63") (name "/I2C1.SDA") (class "Default")
      (node (ref "P2") (pin "11") (pinfunction "11_11") (pintype "bidirectional"))
      (node (ref "U1") (pin "A11") (pinfunction "UART1_RXD_A11") (pintype "bidirectional"))
    )
    (net (code "64") (name "/I2C2.SCL") (class "Default")
      (node (ref "P1") (pin "28") (pinfunction "28_28") (pintype "bidirectional"))
      (node (ref "U1") (pin "A10") (pinfunction "UART1_RTSN_A10") (pintype "bidirectional"))
    )
    (net (code "65") (name "/I2C2.SDA") (class "Default")
      (node (ref "P1") (pin "26") (pinfunction "26_26") (pintype "bidirectional"))
      (node (ref "U1") (pin "B10") (pinfunction "UART1_CTSN_B10") (pintype "bidirectional"))
    )
    (net (code "66") (name "/JTAG_EMU0") (class "Default")
      (node (ref "EMU0") (pin "TP") (pinfunction "TP_TP") (pintype "input"))
      (node (ref "U1") (pin "E2") (pinfunction "EMU0_E2") (pintype "bidirectional"))
    )
    (net (code "67") (name "/JTAG_EMU1") (class "Default")
      (node (ref "EMU1") (pin "TP") (pinfunction "TP_TP") (pintype "input"))
      (node (ref "U1") (pin "E3") (pinfunction "EMU1_E3") (pintype "bidirectional"))
    )
    (net (code "68") (name "/JTAG_TCK") (class "Default")
      (node (ref "TCK") (pin "TP") (pinfunction "TP_TP") (pintype "input"))
      (node (ref "U1") (pin "D1") (pinfunction "TCK_D1") (pintype "bidirectional"))
    )
    (net (code "69") (name "/JTAG_TDI") (class "Default")
      (node (ref "TDI") (pin "TP") (pinfunction "TP_TP") (pintype "input"))
      (node (ref "U1") (pin "C1") (pinfunction "TDI_C1") (pintype "bidirectional"))
    )
    (net (code "70") (name "/JTAG_TDO") (class "Default")
      (node (ref "TDO") (pin "TP") (pinfunction "TP_TP") (pintype "input"))
      (node (ref "U1") (pin "C2") (pinfunction "TDO_C2") (pintype "bidirectional"))
    )
    (net (code "71") (name "/JTAG_TMS") (class "Default")
      (node (ref "TMS") (pin "TP") (pinfunction "TP_TP") (pintype "input"))
      (node (ref "U1") (pin "D2") (pinfunction "TMS_D2") (pintype "bidirectional"))
    )
    (net (code "72") (name "/JTAG_TRST#") (class "Default")
      (node (ref "R12") (pin "2") (pinfunction "2_2") (pintype "bidirectional"))
      (node (ref "TRST") (pin "TP") (pinfunction "TP_TP") (pintype "input"))
      (node (ref "U1") (pin "D3") (pinfunction "TRSTN_D3") (pintype "bidirectional"))
    )
    (net (code "73") (name "/OSC.GND") (class "Default")
      (node (ref "C2") (pin "1") (pinfunction "1_1") (pintype "bidirectional"))
      (node (ref "C3") (pin "1") (pinfunction "1_1") (pintype "bidirectional"))
      (node (ref "U1") (pin "N15") (pinfunction "OSC0_GND_N15") (pintype "bidirectional"))
    )
    (net (code "74") (name "/OSC.IN") (class "Default")
      (node (ref "C2") (pin "2") (pinfunction "2_2") (pintype "bidirectional"))
      (node (ref "R2") (pin "2") (pinfunction "2_2") (pintype "bidirectional"))
      (node (ref "U1") (pin "P16") (pinfunction "OSC0_IN_P16") (pintype "bidirectional"))
      (node (ref "Y1") (pin "2") (pinfunction "P$2_2") (pintype "passive"))
    )
    (net (code "75") (name "/OSC.OUT") (class "Default")
      (node (ref "C3") (pin "2") (pinfunction "2_2") (pintype "bidirectional"))
      (node (ref "R2") (pin "1") (pinfunction "1_1") (pintype "bidirectional"))
      (node (ref "U1") (pin "N16") (pinfunction "OSC0_OUT_N16") (pintype "bidirectional"))
      (node (ref "Y1") (pin "1") (pinfunction "P$1_1") (pintype "passive"))
    )
    (net (code "76") (name "/PMIC_PGOOD") (class "Default")
      (node (ref "U1") (pin "N12") (pinfunction "PMIC_PGOOD_N12") (pintype "output"))
      (node (ref "U1") (pin "P11") (pinfunction "PWRONRSTN_P11") (pintype "bidirectional"))
      (node (ref "U2") (pin "2") (pinfunction "A_2") (pintype "bidirectional"))
    )
    (net (code "77") (name "/PRU0.1") (class "Default")
      (node (ref "P1") (pin "33") (pinfunction "33_33") (pintype "bidirectional"))
      (node (ref "U1") (pin "A2") (pinfunction "MCASP0_FSX_A2") (pintype "bidirectional"))
    )
    (net (code "78") (name "/PRU0.2") (class "Default")
      (node (ref "P2") (pin "32") (pinfunction "32_32") (pintype "bidirectional"))
      (node (ref "U1") (pin "B2") (pinfunction "MCASP0_AXR0_B2") (pintype "bidirectional"))
    )
    (net (code "79") (name "/PRU0.3") (class "Default")
      (node (ref "P2") (pin "30") (pinfunction "30_30") (pintype "bidirectional"))
      (node (ref "U1") (pin "B1") (pinfunction "MCASP0_AHCLKR_B1") (pintype "bidirectional"))
    )
    (net (code "80") (name "/PRU0.4") (class "Default")
      (node (ref "P1") (pin "31") (pinfunction "31_31") (pintype "bidirectional"))
      (node (ref "U1") (pin "A3") (pinfunction "MCASP0_ACLKR_A3") (pintype "bidirectional"))
    )
    (net (code "81") (name "/PRU0.5") (class "Default")
      (node (ref "P2") (pin "34") (pinfunction "34_34") (pintype "bidirectional"))
      (node (ref "U1") (pin "B3") (pinfunction "MCASP0_FSR_B3") (pintype "bidirectional"))
    )
    (net (code "82") (name "/PRU0.6") (class "Default")
      (node (ref "P2") (pin "28") (pinfunction "28_28") (pintype "bidirectional"))
      (node (ref "U1") (pin "C3") (pinfunction "MCASP0_AXR1_C3") (pintype "bidirectional"))
    )
    (net (code "83") (name "/PRU0.7") (class "Default")
      (node (ref "P1") (pin "29") (pinfunction "29_29") (pintype "bidirectional"))
      (node (ref "U1") (pin "C4") (pinfunction "MCASP0_AHCLKX_C4") (pintype "bidirectional"))
    )
    (net (code "84") (name "/PRU1.10") (class "Default")
      (node (ref "P1") (pin "35") (pinfunction "35_35") (pintype "bidirectional"))
      (node (ref "U1") (pin "F1") (pinfunction "LCD_PCLK_F1") (pintype "bidirectional"))
    )
    (net (code "85") (name "/PWM0A") (class "Default")
      (node (ref "P1") (pin "36") (pinfunction "36_36") (pintype "bidirectional"))
      (node (ref "U1") (pin "A1") (pinfunction "MCASP0_ACLKX_A1") (pintype "bidirectional"))
    )
    (net (code "86") (name "/PWM1A") (class "Default")
      (node (ref "P2") (pin "1") (pinfunction "1_1") (pintype "bidirectional"))
      (node (ref "U1") (pin "P12") (pinfunction "GPMC_A2_P12") (pintype "bidirectional"))
    )
    (net (code "87") (name "/PWR.BTN") (class "Default")
      (node (ref "P2") (pin "12") (pinfunction "12_12") (pintype "bidirectional"))
      (node (ref "POWER") (pin "3") (pinfunction "3_3") (pintype "bidirectional"))
      (node (ref "POWER") (pin "4") (pinfunction "4_4") (pintype "bidirectional"))
      (node (ref "U1") (pin "T11") (pinfunction "PMIC_PB_IN_T11") (pintype "bidirectional"))
    )
    (net (code "88") (name "/RESET#") (class "Default")
      (node (ref "P2") (pin "26") (pinfunction "26_26") (pintype "bidirectional"))
      (node (ref "U1") (pin "R11") (pinfunction "WARMRSTN_R11") (pintype "bidirectional"))
      (node (ref "U2") (pin "4") (pinfunction "Y_4") (pintype "bidirectional"))
    )
    (net (code "89") (name "/SPI0.CLK") (class "Default")
      (node (ref "P1") (pin "8") (pinfunction "8_8") (pintype "bidirectional"))
      (node (ref "U1") (pin "A13") (pinfunction "SPI0_SCLK_A13") (pintype "bidirectional"))
    )
    (net (code "90") (name "/SPI0.CS") (class "Default")
      (node (ref "P1") (pin "6") (pinfunction "6_6") (pintype "bidirectional"))
      (node (ref "U1") (pin "A14") (pinfunction "SPI0_CS0_A14") (pintype "bidirectional"))
    )
    (net (code "91") (name "/SPI0.MISO") (class "Default")
      (node (ref "P1") (pin "10") (pinfunction "10_10") (pintype "bidirectional"))
      (node (ref "U1") (pin "B13") (pinfunction "SPI0_D0_B13") (pintype "bidirectional"))
    )
    (net (code "92") (name "/SPI0.MOSI") (class "Default")
      (node (ref "P1") (pin "12") (pinfunction "12_12") (pintype "bidirectional"))
      (node (ref "U1") (pin "B14") (pinfunction "SPI0_D1_B14") (pintype "bidirectional"))
    )
    (net (code "93") (name "/SPI1.CLK") (class "Default")
      (node (ref "P2") (pin "29") (pinfunction "29_29") (pintype "bidirectional"))
      (node (ref "U1") (pin "C5") (pinfunction "ECAP0_IN_PWM0_OUT_C5") (pintype "bidirectional"))
    )
    (net (code "94") (name "/SPI1.CS") (class "Default")
      (node (ref "P2") (pin "31") (pinfunction "31_31") (pintype "bidirectional"))
      (node (ref "U1") (pin "A4") (pinfunction "XDMA_EVENT_INTR0_A4") (pintype "bidirectional"))
    )
    (net (code "95") (name "/SPI1.MISO") (class "Default")
      (node (ref "P2") (pin "27") (pinfunction "27_27") (pintype "bidirectional"))
      (node (ref "U1") (pin "C12") (pinfunction "UART0_CTSN_C12") (pintype "bidirectional"))
    )
    (net (code "96") (name "/SPI1.MOSI") (class "Default")
      (node (ref "P2") (pin "25") (pinfunction "25_25") (pintype "bidirectional"))
      (node (ref "U1") (pin "C13") (pinfunction "UART0_RTSN_C13") (pintype "bidirectional"))
    )
    (net (code "97") (name "/UART0.RX") (class "Default")
      (node (ref "P1") (pin "32") (pinfunction "32_32") (pintype "bidirectional"))
      (node (ref "U1") (pin "A12") (pinfunction "UART0_RXD_A12") (pintype "bidirectional"))
    )
    (net (code "98") (name "/UART0.TX") (class "Default")
      (node (ref "P1") (pin "30") (pinfunction "30_30") (pintype "bidirectional"))
      (node (ref "U1") (pin "B12") (pinfunction "UART0_TXD_B12") (pintype "bidirectional"))
    )
    (net (code "99") (name "/UART4.RX") (class "Default")
      (node (ref "P2") (pin "5") (pinfunction "5_5") (pintype "bidirectional"))
      (node (ref "U1") (pin "P15") (pinfunction "GPMC_WAIT0_P15") (pintype "bidirectional"))
    )
    (net (code "100") (name "/UART4.TX") (class "Default")
      (node (ref "P2") (pin "7") (pinfunction "7_7") (pintype "bidirectional"))
      (node (ref "U1") (pin "R16") (pinfunction "GPMC_WPN_R16") (pintype "bidirectional"))
    )
    (net (code "101") (name "/USB1.D+") (class "Default")
      (node (ref "P1") (pin "11") (pinfunction "11_11") (pintype "bidirectional"))
      (node (ref "U1") (pin "L15") (pinfunction "USB1_DP_L15") (pintype "bidirectional"))
    )
    (net (code "102") (name "/USB1.D-") (class "Default")
      (node (ref "P1") (pin "9") (pinfunction "9_9") (pintype "bidirectional"))
      (node (ref "U1") (pin "L16") (pinfunction "USB1_DM_L16") (pintype "bidirectional"))
    )
    (net (code "103") (name "/USB1.DRVVBUS") (class "Default")
      (node (ref "P1") (pin "3") (pinfunction "3_3") (pintype "bidirectional"))
      (node (ref "U1") (pin "M14") (pinfunction "USB1_DRVVBUS_M14") (pintype "bidirectional"))
    )
    (net (code "104") (name "/USB1.ID") (class "Default")
      (node (ref "P1") (pin "13") (pinfunction "13_13") (pintype "bidirectional"))
      (node (ref "U1") (pin "L14") (pinfunction "USB1_ID_L14") (pintype "bidirectional"))
    )
    (net (code "105") (name "/USB1.VBUS") (class "Default")
      (node (ref "P1") (pin "5") (pinfunction "5_5") (pintype "bidirectional"))
      (node (ref "U1") (pin "M15") (pinfunction "USB1_VBUS_M15") (pintype "bidirectional"))
    )
    (net (code "106") (name "3.3V") (class "Default")
      (node (ref "C5") (pin "1") (pinfunction "1_1") (pintype "bidirectional"))
      (node (ref "C6") (pin "1") (pinfunction "1_1") (pintype "bidirectional"))
      (node (ref "P1") (pin "14") (pinfunction "14_14") (pintype "bidirectional"))
      (node (ref "P2") (pin "23") (pinfunction "23_23") (pintype "bidirectional"))
      (node (ref "R10") (pin "5") (pinfunction "5_5") (pintype "bidirectional"))
      (node (ref "R10") (pin "6") (pinfunction "6_6") (pintype "bidirectional"))
      (node (ref "R10") (pin "7") (pinfunction "7_7") (pintype "bidirectional"))
      (node (ref "R10") (pin "8") (pinfunction "8_8") (pintype "bidirectional"))
      (node (ref "R11") (pin "2") (pinfunction "2_2") (pintype "bidirectional"))
      (node (ref "R11") (pin "3") (pinfunction "3_3") (pintype "bidirectional"))
      (node (ref "R11") (pin "4") (pinfunction "4_4") (pintype "bidirectional"))
      (node (ref "R6") (pin "7") (pinfunction "7_7") (pintype "bidirectional"))
      (node (ref "R8") (pin "5") (pinfunction "5_5") (pintype "bidirectional"))
      (node (ref "R9") (pin "4") (pinfunction "4_4") (pintype "bidirectional"))
      (node (ref "U1") (pin "F6") (pinfunction "SYS_VDD1_3P3V_F6") (pintype "power_in"))
      (node (ref "U1") (pin "F7") (pinfunction "SYS_VDD1_3P3V_F7") (pintype "power_in"))
      (node (ref "U1") (pin "G6") (pinfunction "SYS_VDD1_3P3V_G6") (pintype "power_in"))
      (node (ref "U1") (pin "G7") (pinfunction "SYS_VDD1_3P3V_G7") (pintype "power_in"))
      (node (ref "X2") (pin "4") (pinfunction "VDD_4") (pintype "bidirectional"))
    )
    (net (code "107") (name "CGND") (class "Default")
      (node (ref "FB2") (pin "1") (pinfunction "P$1_1") (pintype "bidirectional"))
      (node (ref "X1") (pin "CGND1") (pinfunction "SGND1_CGND1") (pintype "bidirectional"))
      (node (ref "X1") (pin "CGND2") (pinfunction "SGND2_CGND2") (pintype "bidirectional"))
      (node (ref "X1") (pin "CGND3") (pinfunction "SGND3_CGND3") (pintype "bidirectional"))
      (node (ref "X1") (pin "CGND4") (pinfunction "SGND4_CGND4") (pintype "bidirectional"))
      (node (ref "X1") (pin "CGND5") (pinfunction "SGND5_CGND5") (pintype "bidirectional"))
      (node (ref "X1") (pin "CGND6") (pinfunction "SGND6_CGND6") (pintype "bidirectional"))
      (node (ref "X2") (pin "G1") (pinfunction "G1_G1") (pintype "bidirectional"))
      (node (ref "X2") (pin "G2") (pinfunction "G2_G2") (pintype "bidirectional"))
      (node (ref "X2") (pin "G3") (pinfunction "G3_G3") (pintype "bidirectional"))
      (node (ref "X2") (pin "G4") (pinfunction "G4_G4") (pintype "bidirectional"))
    )
    (net (code "108") (name "GND") (class "Default")
      (node (ref "C1") (pin "2") (pinfunction "2_2") (pintype "bidirectional"))
      (node (ref "C4") (pin "2") (pinfunction "2_2") (pintype "bidirectional"))
      (node (ref "C5") (pin "2") (pinfunction "2_2") (pintype "bidirectional"))
      (node (ref "C6") (pin "2") (pinfunction "2_2") (pintype "bidirectional"))
      (node (ref "FB2") (pin "2") (pinfunction "P$2_2") (pintype "bidirectional"))
      (node (ref "P1") (pin "15") (pinfunction "15_15") (pintype "bidirectional"))
      (node (ref "P1") (pin "16") (pinfunction "16_16") (pintype "bidirectional"))
      (node (ref "P1") (pin "22") (pinfunction "22_22") (pintype "bidirectional"))
      (node (ref "P2") (pin "15") (pinfunction "15_15") (pintype "bidirectional"))
      (node (ref "P2") (pin "21") (pinfunction "21_21") (pintype "bidirectional"))
      (node (ref "POWER") (pin "1") (pinfunction "1_1") (pintype "bidirectional"))
      (node (ref "POWER") (pin "2") (pinfunction "2_2") (pintype "bidirectional"))
      (node (ref "R1") (pin "1") (pinfunction "1_1") (pintype "bidirectional"))
      (node (ref "R12") (pin "1") (pinfunction "1_1") (pintype "bidirectional"))
      (node (ref "R3") (pin "1") (pinfunction "1_1") (pintype "bidirectional"))
      (node (ref "R4") (pin "5") (pinfunction "5_5") (pintype "bidirectional"))
      (node (ref "R4") (pin "6") (pinfunction "6_6") (pintype "bidirectional"))
      (node (ref "R4") (pin "7") (pinfunction "7_7") (pintype "bidirectional"))
      (node (ref "R4") (pin "8") (pinfunction "8_8") (pintype "bidirectional"))
      (node (ref "R5") (pin "5") (pinfunction "5_5") (pintype "bidirectional"))
      (node (ref "R5") (pin "8") (pinfunction "8_8") (pintype "bidirectional"))
      (node (ref "R6") (pin "5") (pinfunction "5_5") (pintype "bidirectional"))
      (node (ref "R6") (pin "6") (pinfunction "6_6") (pintype "bidirectional"))
      (node (ref "R6") (pin "8") (pinfunction "8_8") (pintype "bidirectional"))
      (node (ref "R7") (pin "5") (pinfunction "5_5") (pintype "bidirectional"))
      (node (ref "R7") (pin "6") (pinfunction "6_6") (pintype "bidirectional"))
      (node (ref "R7") (pin "7") (pinfunction "7_7") (pintype "bidirectional"))
      (node (ref "R7") (pin "8") (pinfunction "8_8") (pintype "bidirectional"))
      (node (ref "R8") (pin "6") (pinfunction "6_6") (pintype "bidirectional"))
      (node (ref "R8") (pin "7") (pinfunction "7_7") (pintype "bidirectional"))
      (node (ref "R8") (pin "8") (pinfunction "8_8") (pintype "bidirectional"))
      (node (ref "R9") (pin "1") (pinfunction "1_1") (pintype "bidirectional"))
      (node (ref "R9") (pin "2") (pinfunction "2_2") (pintype "bidirectional"))
      (node (ref "R9") (pin "3") (pinfunction "3_3") (pintype "bidirectional"))
      (node (ref "U1") (pin "D8") (pinfunction "DGND_D8") (pintype "bidirectional"))
      (node (ref "U1") (pin "D9") (pinfunction "DGND_D9") (pintype "bidirectional"))
      (node (ref "U1") (pin "E10") (pinfunction "DGND_E10") (pintype "bidirectional"))
      (node (ref "U1") (pin "E11") (pinfunction "DGND_E11") (pintype "bidirectional"))
      (node (ref "U1") (pin "E12") (pinfunction "DGND_E12") (pintype "bidirectional"))
      (node (ref "U1") (pin "E5") (pinfunction "DGND_E5") (pintype "bidirectional"))
      (node (ref "U1") (pin "E6") (pinfunction "DGND_E6") (pintype "bidirectional"))
      (node (ref "U1") (pin "E7") (pinfunction "DGND_E7") (pintype "bidirectional"))
      (node (ref "U1") (pin "E8") (pinfunction "DGND_E8") (pintype "bidirectional"))
      (node (ref "U1") (pin "E9") (pinfunction "DGND_E9") (pintype "bidirectional"))
      (node (ref "U1") (pin "F12") (pinfunction "DGND_F12") (pintype "bidirectional"))
      (node (ref "U1") (pin "F5") (pinfunction "DGND_F5") (pintype "bidirectional"))
      (node (ref "U1") (pin "G12") (pinfunction "DGND_G12") (pintype "bidirectional"))
      (node (ref "U1") (pin "G5") (pinfunction "DGND_G5") (pintype "bidirectional"))
      (node (ref "U1") (pin "H12") (pinfunction "DGND_H12") (pintype "bidirectional"))
      (node (ref "U1") (pin "H13") (pinfunction "DGND_H13") (pintype "bidirectional"))
      (node (ref "U1") (pin "H4") (pinfunction "DGND_H4") (pintype "bidirectional"))
      (node (ref "U1") (pin "H5") (pinfunction "DGND_H5") (pintype "bidirectional"))
      (node (ref "U1") (pin "J12") (pinfunction "DGND_J12") (pintype "bidirectional"))
      (node (ref "U1") (pin "J13") (pinfunction "DGND_J13") (pintype "bidirectional"))
      (node (ref "U1") (pin "J4") (pinfunction "DGND_J4") (pintype "bidirectional"))
      (node (ref "U1") (pin "J5") (pinfunction "DGND_J5") (pintype "bidirectional"))
      (node (ref "U1") (pin "K12") (pinfunction "DGND_K12") (pintype "bidirectional"))
      (node (ref "U1") (pin "K5") (pinfunction "DGND_K5") (pintype "bidirectional"))
      (node (ref "U1") (pin "L12") (pinfunction "DGND_L12") (pintype "bidirectional"))
      (node (ref "U1") (pin "L5") (pinfunction "DGND_L5") (pintype "bidirectional"))
      (node (ref "U1") (pin "M10") (pinfunction "DGND_M10") (pintype "bidirectional"))
      (node (ref "U1") (pin "M11") (pinfunction "DGND_M11") (pintype "bidirectional"))
      (node (ref "U1") (pin "M12") (pinfunction "DGND_M12") (pintype "bidirectional"))
      (node (ref "U1") (pin "M5") (pinfunction "DGND_M5") (pintype "bidirectional"))
      (node (ref "U1") (pin "M6") (pinfunction "DGND_M6") (pintype "bidirectional"))
      (node (ref "U1") (pin "M7") (pinfunction "DGND_M7") (pintype "bidirectional"))
      (node (ref "U1") (pin "M8") (pinfunction "DGND_M8") (pintype "bidirectional"))
      (node (ref "U1") (pin "M9") (pinfunction "DGND_M9") (pintype "bidirectional"))
      (node (ref "U1") (pin "N8") (pinfunction "DGND_N8") (pintype "bidirectional"))
      (node (ref "U1") (pin "N9") (pinfunction "DGND_N9") (pintype "bidirectional"))
      (node (ref "U2") (pin "3") (pinfunction "GND_3") (pintype "bidirectional"))
      (node (ref "U3") (pin "4") (pinfunction "GND_4") (pintype "bidirectional"))
      (node (ref "X1") (pin "GND") (pinfunction "GND_GND") (pintype "input"))
      (node (ref "X2") (pin "6") (pinfunction "VSS_6") (pintype "bidirectional"))
    )
    (net (code "109") (name "Net-(FB1-P$1)") (class "Default")
      (node (ref "FB1") (pin "1") (pinfunction "P$1_1") (pintype "bidirectional"))
      (node (ref "X1") (pin "VBUS") (pinfunction "VBUS_VBUS") (pintype "input"))
    )
    (net (code "110") (name "Net-(PWR-PadK)") (class "Default")
      (node (ref "PWR") (pin "K") (pinfunction "K_K") (pintype "passive"))
      (node (ref "R1") (pin "2") (pinfunction "2_2") (pintype "bidirectional"))
    )
    (net (code "111") (name "Net-(R4-Pad1)") (class "Default")
      (node (ref "R4") (pin "1") (pinfunction "1_1") (pintype "bidirectional"))
      (node (ref "USR0") (pin "K") (pinfunction "K_K") (pintype "passive"))
    )
    (net (code "112") (name "Net-(R4-Pad2)") (class "Default")
      (node (ref "R4") (pin "2") (pinfunction "2_2") (pintype "bidirectional"))
      (node (ref "USR1") (pin "K") (pinfunction "K_K") (pintype "passive"))
    )
    (net (code "113") (name "Net-(R4-Pad3)") (class "Default")
      (node (ref "R4") (pin "3") (pinfunction "3_3") (pintype "bidirectional"))
      (node (ref "USR2") (pin "K") (pinfunction "K_K") (pintype "passive"))
    )
    (net (code "114") (name "Net-(R4-Pad4)") (class "Default")
      (node (ref "R4") (pin "4") (pinfunction "4_4") (pintype "bidirectional"))
      (node (ref "USR3") (pin "K") (pinfunction "K_K") (pintype "passive"))
    )
    (net (code "115") (name "Net-(U1A-EXTINTN)") (class "Default")
      (node (ref "U1") (pin "D4") (pinfunction "EXTINTN_D4") (pintype "bidirectional"))
      (node (ref "U1") (pin "E4") (pinfunction "PMIC_NINT_E4") (pintype "output"))
    )
    (net (code "116") (name "Net-(U1A-EXT_WAKEUP)") (class "Default")
      (node (ref "U1") (pin "L4") (pinfunction "PMIC_NWAKEUP_L4") (pintype "output"))
      (node (ref "U1") (pin "M4") (pinfunction "EXT_WAKEUP_M4") (pintype "bidirectional"))
    )
    (net (code "117") (name "Net-(U1A-I2C0_SCL)") (class "Default")
      (node (ref "U1") (pin "C10") (pinfunction "I2C0_SCL_C10") (pintype "bidirectional"))
      (node (ref "U1") (pin "D10") (pinfunction "PMIC_SCL_D10") (pintype "bidirectional"))
    )
    (net (code "118") (name "Net-(U1A-I2C0_SDA)") (class "Default")
      (node (ref "U1") (pin "C11") (pinfunction "I2C0_SDA_C11") (pintype "bidirectional"))
      (node (ref "U1") (pin "D11") (pinfunction "PMIC_SDA_D11") (pintype "bidirectional"))
    )
    (net (code "119") (name "Net-(U1A-PMIC_LDO_PGOOD)") (class "Default")
      (node (ref "U1") (pin "N4") (pinfunction "PMIC_LDO_PGOOD_N4") (pintype "output"))
      (node (ref "U1") (pin "N5") (pinfunction "RTC_PWRONRSTN_N5") (pintype "bidirectional"))
    )
    (net (code "120") (name "Net-(U1A-PMIC_POWER_EN)") (class "Default")
      (node (ref "U1") (pin "N10") (pinfunction "PMIC_POWER_EN_N10") (pintype "output"))
      (node (ref "U1") (pin "N11") (pinfunction "PMIC_PWR_EN_N11") (pintype "input"))
    )
    (net (code "121") (name "Net-(U1A-RTC_KALDO_ENN)") (class "Default")
      (node (ref "R3") (pin "2") (pinfunction "2_2") (pintype "bidirectional"))
      (node (ref "U1") (pin "M16") (pinfunction "RTC_KALDO_ENN_M16") (pintype "bidirectional"))
    )
    (net (code "122") (name "Net-(U1B-AIN7)") (class "Default")
      (node (ref "U1") (pin "D6") (pinfunction "PMIC_MUX_OUT_D6") (pintype "bidirectional"))
      (node (ref "U1") (pin "D7") (pinfunction "AIN7_D7") (pintype "bidirectional"))
    )
    (net (code "123") (name "Net-(U1F-VDDS_DDR)") (class "Default")
      (node (ref "TP1") (pin "TP") (pinfunction "TP_TP") (pintype "input"))
      (node (ref "U1") (pin "F4") (pinfunction "VDDS_DDR_F4") (pintype "bidirectional"))
    )
    (net (code "124") (name "Net-(U1F-VDDS_PLL)") (class "Default")
      (node (ref "TP4") (pin "TP") (pinfunction "TP_TP") (pintype "input"))
      (node (ref "U1") (pin "G13") (pinfunction "VDDS_PLL_G13") (pintype "bidirectional"))
    )
    (net (code "125") (name "Net-(U1F-VDD_CORE)") (class "Default")
      (node (ref "TP2") (pin "TP") (pinfunction "TP_TP") (pintype "input"))
      (node (ref "U1") (pin "G4") (pinfunction "VDD_CORE_G4") (pintype "bidirectional"))
    )
    (net (code "126") (name "Net-(U1F-VDD_MPU)") (class "Default")
      (node (ref "TP3") (pin "TP") (pinfunction "TP_TP") (pintype "input"))
      (node (ref "U1") (pin "F13") (pinfunction "VDD_MPU_F13") (pintype "bidirectional"))
    )
    (net (code "127") (name "USB1.VIN") (class "Default")
      (node (ref "C4") (pin "1") (pinfunction "1_1") (pintype "bidirectional"))
      (node (ref "FB1") (pin "2") (pinfunction "P$2_2") (pintype "bidirectional"))
      (node (ref "P1") (pin "7") (pinfunction "7_7") (pintype "bidirectional"))
      (node (ref "U1") (pin "J16") (pinfunction "USB0_VBUS_J16") (pintype "bidirectional"))
      (node (ref "U1") (pin "P9") (pinfunction "VIN_USB_P9") (pintype "power_in"))
      (node (ref "U1") (pin "R9") (pinfunction "VIN_USB_R9") (pintype "power_in"))
      (node (ref "U1") (pin "T9") (pinfunction "VIN_USB_T9") (pintype "power_in"))
      (node (ref "U3") (pin "6") (pinfunction "VBUS_6") (pintype "bidirectional"))
    )
    (net (code "128") (name "VDD_1V8") (class "Default")
      (node (ref "U1") (pin "F10") (pinfunction "SYS_VDD_1P8V_F10") (pintype "power_in"))
      (node (ref "U1") (pin "G10") (pinfunction "SYS_VDD_1P8V_G10") (pintype "power_in"))
      (node (ref "U1") (pin "H10") (pinfunction "SYS_VDD_1P8V_H10") (pintype "power_in"))
      (node (ref "U1") (pin "H11") (pinfunction "SYS_VDD_1P8V_H11") (pintype "power_in"))
      (node (ref "U1") (pin "J10") (pinfunction "SYS_VDD_1P8V_J10") (pintype "power_in"))
      (node (ref "U1") (pin "J11") (pinfunction "SYS_VDD_1P8V_J11") (pintype "power_in"))
      (node (ref "U1") (pin "K10") (pinfunction "SYS_VDD_1P8V_K10") (pintype "power_in"))
      (node (ref "U1") (pin "L10") (pinfunction "SYS_VDD_1P8V_L10") (pintype "power_in"))
    )
    (net (code "129") (name "VDD_3V3A") (class "Default")
      (node (ref "U1") (pin "F8") (pinfunction "SYS_VDD3_3P3V_F8") (pintype "power_in"))
      (node (ref "U1") (pin "F9") (pinfunction "VDDSHV4_F9") (pintype "power_in"))
      (node (ref "U1") (pin "G8") (pinfunction "SYS_VDD3_3P3V_G8") (pintype "power_in"))
      (node (ref "U1") (pin "G9") (pinfunction "VDDSHV5_G9") (pintype "power_in"))
      (node (ref "U1") (pin "H7") (pinfunction "SYS_VDD3_3P3V_H7") (pintype "power_in"))
      (node (ref "U1") (pin "H8") (pinfunction "SYS_VDD3_3P3V_H8") (pintype "power_in"))
      (node (ref "U1") (pin "H9") (pinfunction "VDDSHV6_H9") (pintype "power_in"))
      (node (ref "U1") (pin "J7") (pinfunction "SYS_VDD3_3P3V_J7") (pintype "power_in"))
      (node (ref "U1") (pin "J8") (pinfunction "SYS_VDD3_3P3V_J8") (pintype "power_in"))
      (node (ref "U1") (pin "J9") (pinfunction "VDDSHV1_J9") (pintype "power_in"))
      (node (ref "U1") (pin "K8") (pinfunction "SYS_VDD3_3P3V_K8") (pintype "power_in"))
      (node (ref "U1") (pin "K9") (pinfunction "VDDSHV2_K9") (pintype "power_in"))
      (node (ref "U1") (pin "L8") (pinfunction "SYS_VDD3_3P3V_L8") (pintype "power_in"))
      (node (ref "U1") (pin "L9") (pinfunction "VDDSHV3_L9") (pintype "power_in"))
    )
    (net (code "130") (name "VDD_3V3AUX") (class "Default")
      (node (ref "PWR") (pin "A") (pinfunction "A_A") (pintype "passive"))
      (node (ref "U1") (pin "F11") (pinfunction "SYS_VDD2_3P3V_F11") (pintype "power_in"))
      (node (ref "U1") (pin "G11") (pinfunction "SYS_VDD2_3P3V_G11") (pintype "power_in"))
    )
    (net (code "131") (name "VDD_RTC") (class "Default")
      (node (ref "C1") (pin "1") (pinfunction "1_1") (pintype "bidirectional"))
      (node (ref "U1") (pin "K11") (pinfunction "SYS_RTC_1P8V_K11") (pintype "power_in"))
      (node (ref "U1") (pin "L11") (pinfunction "SYS_RTC_1P8V_L11") (pintype "power_in"))
      (node (ref "U2") (pin "5") (pinfunction "VCC_5") (pintype "bidirectional"))
    )
    (net (code "132") (name "VIN") (class "Default")
      (node (ref "P1") (pin "1") (pinfunction "1_1") (pintype "bidirectional"))
      (node (ref "U1") (pin "P10") (pinfunction "VIN_AC_P10") (pintype "power_in"))
      (node (ref "U1") (pin "R10") (pinfunction "VIN_AC_R10") (pintype "power_in"))
      (node (ref "U1") (pin "T10") (pinfunction "VIN_AC_T10") (pintype "power_in"))
    )
    (net (code "133") (name "VOUT") (class "Default")
      (node (ref "P1") (pin "24") (pinfunction "24_24") (pintype "bidirectional"))
      (node (ref "P2") (pin "13") (pinfunction "13_13") (pintype "bidirectional"))
      (node (ref "U1") (pin "K6") (pinfunction "SYS_VOUT_K6") (pintype "power_in"))
      (node (ref "U1") (pin "K7") (pinfunction "SYS_VOUT_K7") (pintype "power_in"))
      (node (ref "U1") (pin "L6") (pinfunction "SYS_VOUT_L6") (pintype "power_in"))
      (node (ref "U1") (pin "L7") (pinfunction "SYS_VOUT_L7") (pintype "power_in"))
    )
    (net (code "134") (name "unconnected-(FUD1-PadP$1)") (class "Default")
      (node (ref "FUD1") (pin "P$1") (pinfunction "P$1_P$1") (pintype "no_connect"))
    )
    (net (code "135") (name "unconnected-(FUD2-PadP$1)") (class "Default")
      (node (ref "FUD2") (pin "P$1") (pinfunction "P$1_P$1") (pintype "no_connect"))
    )
    (net (code "136") (name "unconnected-(FUD3-PadP$1)") (class "Default")
      (node (ref "FUD3") (pin "P$1") (pinfunction "P$1_P$1") (pintype "no_connect"))
    )
    (net (code "137") (name "unconnected-(R11-Pad1)") (class "Default")
      (node (ref "R11") (pin "1") (pinfunction "1_1") (pintype "bidirectional"))
    )
    (net (code "138") (name "unconnected-(R11-Pad8)") (class "Default")
      (node (ref "R11") (pin "8") (pinfunction "8_8") (pintype "bidirectional"))
    )
    (net (code "139") (name "unconnected-(U1A-PMIC_NRESET-PadM13)") (class "Default")
      (node (ref "U1") (pin "M13") (pinfunction "PMIC_NRESET_M13") (pintype "bidirectional"))
    )
    (net (code "140") (name "unconnected-(U1B-OSC1_GND-PadB5)") (class "Default")
      (node (ref "U1") (pin "B5") (pinfunction "OSC1_GND_B5") (pintype "bidirectional"))
    )
    (net (code "141") (name "unconnected-(U1B-OSC1_IN-PadA6)") (class "Default")
      (node (ref "U1") (pin "A6") (pinfunction "OSC1_IN_A6") (pintype "bidirectional"))
    )
    (net (code "142") (name "unconnected-(U1B-OSC1_OUT-PadA5)") (class "Default")
      (node (ref "U1") (pin "A5") (pinfunction "OSC1_OUT_A5") (pintype "bidirectional"))
    )
    (net (code "143") (name "unconnected-(U1B-USB0_CE-PadK13)") (class "Default")
      (node (ref "U1") (pin "K13") (pinfunction "USB0_CE_K13") (pintype "bidirectional"))
    )
    (net (code "144") (name "unconnected-(U1B-USB0_DRVVBUS-PadJ15)") (class "Default")
      (node (ref "U1") (pin "J15") (pinfunction "USB0_DRVVBUS_J15") (pintype "bidirectional"))
    )
    (net (code "145") (name "unconnected-(U1B-USB1_CE-PadL13)") (class "Default")
      (node (ref "U1") (pin "L13") (pinfunction "USB1_CE_L13") (pintype "bidirectional"))
    )
    (net (code "146") (name "unconnected-(U1C-GPMC_A0-PadT12)") (class "Default")
      (node (ref "U1") (pin "T12") (pinfunction "GPMC_A0_T12") (pintype "bidirectional"))
    )
    (net (code "147") (name "unconnected-(U1C-GPMC_A1-PadR12)") (class "Default")
      (node (ref "U1") (pin "R12") (pinfunction "GPMC_A1_R12") (pintype "bidirectional"))
    )
    (net (code "148") (name "unconnected-(U1C-GPMC_A3-PadT13)") (class "Default")
      (node (ref "U1") (pin "T13") (pinfunction "GPMC_A3_T13") (pintype "bidirectional"))
    )
    (net (code "149") (name "unconnected-(U1C-GPMC_AD0-PadR3)") (class "Default")
      (node (ref "U1") (pin "R3") (pinfunction "GPMC_AD0_R3") (pintype "bidirectional"))
    )
    (net (code "150") (name "unconnected-(U1C-GPMC_AD1-PadR2)") (class "Default")
      (node (ref "U1") (pin "R2") (pinfunction "GPMC_AD1_R2") (pintype "bidirectional"))
    )
    (net (code "151") (name "unconnected-(U1C-GPMC_AD2-PadR1)") (class "Default")
      (node (ref "U1") (pin "R1") (pinfunction "GPMC_AD2_R1") (pintype "bidirectional"))
    )
    (net (code "152") (name "unconnected-(U1C-GPMC_AD3-PadT3)") (class "Default")
      (node (ref "U1") (pin "T3") (pinfunction "GPMC_AD3_T3") (pintype "bidirectional"))
    )
    (net (code "153") (name "unconnected-(U1C-GPMC_AD4-PadT2)") (class "Default")
      (node (ref "U1") (pin "T2") (pinfunction "GPMC_AD4_T2") (pintype "bidirectional"))
    )
    (net (code "154") (name "unconnected-(U1C-GPMC_AD5-PadT1)") (class "Default")
      (node (ref "U1") (pin "T1") (pinfunction "GPMC_AD5_T1") (pintype "bidirectional"))
    )
    (net (code "155") (name "unconnected-(U1C-GPMC_AD6-PadP4)") (class "Default")
      (node (ref "U1") (pin "P4") (pinfunction "GPMC_AD6_P4") (pintype "bidirectional"))
    )
    (net (code "156") (name "unconnected-(U1C-GPMC_AD7-PadR4)") (class "Default")
      (node (ref "U1") (pin "R4") (pinfunction "GPMC_AD7_R4") (pintype "bidirectional"))
    )
    (net (code "157") (name "unconnected-(U1C-GPMC_AD8-PadT4)") (class "Default")
      (node (ref "U1") (pin "T4") (pinfunction "GPMC_AD8_T4") (pintype "bidirectional"))
    )
    (net (code "158") (name "unconnected-(U1C-GPMC_ADVN_ALE-PadM1)") (class "Default")
      (node (ref "U1") (pin "M1") (pinfunction "GPMC_ADVN_ALE_M1") (pintype "bidirectional"))
    )
    (net (code "159") (name "unconnected-(U1C-GPMC_CSN0-PadP3)") (class "Default")
      (node (ref "U1") (pin "P3") (pinfunction "GPMC_CSN0_P3") (pintype "bidirectional"))
    )
    (net (code "160") (name "unconnected-(U1C-GPMC_CSN1-PadP2)") (class "Default")
      (node (ref "U1") (pin "P2") (pinfunction "GPMC_CSN1_P2") (pintype "bidirectional"))
    )
    (net (code "161") (name "unconnected-(U1C-GPMC_CSN2-PadP1)") (class "Default")
      (node (ref "U1") (pin "P1") (pinfunction "GPMC_CSN2_P1") (pintype "bidirectional"))
    )
    (net (code "162") (name "unconnected-(U1C-GPMC_OEN_REN-PadN1)") (class "Default")
      (node (ref "U1") (pin "N1") (pinfunction "GPMC_OEN_REN_N1") (pintype "bidirectional"))
    )
    (net (code "163") (name "unconnected-(U1C-GPMC_WEN-PadN2)") (class "Default")
      (node (ref "U1") (pin "N2") (pinfunction "GPMC_WEN_N2") (pintype "bidirectional"))
    )
    (net (code "164") (name "unconnected-(U1D-MDC-PadD13)") (class "Default")
      (node (ref "U1") (pin "D13") (pinfunction "MDC_D13") (pintype "bidirectional"))
    )
    (net (code "165") (name "unconnected-(U1D-MDIO-PadE13)") (class "Default")
      (node (ref "U1") (pin "E13") (pinfunction "MDIO_E13") (pintype "bidirectional"))
    )
    (net (code "166") (name "unconnected-(U1D-MII1_COL-PadF15)") (class "Default")
      (node (ref "U1") (pin "F15") (pinfunction "MII1_COL_F15") (pintype "bidirectional"))
    )
    (net (code "167") (name "unconnected-(U1D-MII1_CRS-PadF14)") (class "Default")
      (node (ref "U1") (pin "F14") (pinfunction "MII1_CRS_F14") (pintype "bidirectional"))
    )
    (net (code "168") (name "unconnected-(U1D-MII1_RXD0-PadE14)") (class "Default")
      (node (ref "U1") (pin "E14") (pinfunction "MII1_RXD0_E14") (pintype "bidirectional"))
    )
    (net (code "169") (name "unconnected-(U1D-MII1_RXD1-PadD16)") (class "Default")
      (node (ref "U1") (pin "D16") (pinfunction "MII1_RXD1_D16") (pintype "bidirectional"))
    )
    (net (code "170") (name "unconnected-(U1D-MII1_RXD2-PadD15)") (class "Default")
      (node (ref "U1") (pin "D15") (pinfunction "MII1_RXD2_D15") (pintype "bidirectional"))
    )
    (net (code "171") (name "unconnected-(U1D-MII1_RXD3-PadD14)") (class "Default")
      (node (ref "U1") (pin "D14") (pinfunction "MII1_RXD3_D14") (pintype "bidirectional"))
    )
    (net (code "172") (name "unconnected-(U1D-MII1_RX_CLK-PadE16)") (class "Default")
      (node (ref "U1") (pin "E16") (pinfunction "MII1_RX_CLK_E16") (pintype "bidirectional"))
    )
    (net (code "173") (name "unconnected-(U1D-MII1_RX_DV-PadF16)") (class "Default")
      (node (ref "U1") (pin "F16") (pinfunction "MII1_RX_DV_F16") (pintype "bidirectional"))
    )
    (net (code "174") (name "unconnected-(U1D-MII1_RX_ER-PadE15)") (class "Default")
      (node (ref "U1") (pin "E15") (pinfunction "MII1_RX_ER_E15") (pintype "bidirectional"))
    )
    (net (code "175") (name "unconnected-(U1D-MII1_TXD0-PadH15)") (class "Default")
      (node (ref "U1") (pin "H15") (pinfunction "MII1_TXD0_H15") (pintype "bidirectional"))
    )
    (net (code "176") (name "unconnected-(U1D-MII1_TXD1-PadH14)") (class "Default")
      (node (ref "U1") (pin "H14") (pinfunction "MII1_TXD1_H14") (pintype "bidirectional"))
    )
    (net (code "177") (name "unconnected-(U1D-MII1_TXD2-PadG16)") (class "Default")
      (node (ref "U1") (pin "G16") (pinfunction "MII1_TXD2_G16") (pintype "bidirectional"))
    )
    (net (code "178") (name "unconnected-(U1D-MII1_TXD3-PadG15)") (class "Default")
      (node (ref "U1") (pin "G15") (pinfunction "MII1_TXD3_G15") (pintype "bidirectional"))
    )
    (net (code "179") (name "unconnected-(U1D-MII1_TX_CLK-PadH16)") (class "Default")
      (node (ref "U1") (pin "H16") (pinfunction "MII1_TX_CLK_H16") (pintype "bidirectional"))
    )
    (net (code "180") (name "unconnected-(U1D-MII1_TX_EN-PadG14)") (class "Default")
      (node (ref "U1") (pin "G14") (pinfunction "MII1_TX_EN_G14") (pintype "bidirectional"))
    )
    (net (code "181") (name "unconnected-(U1D-RMII1_REF_CLK-PadJ14)") (class "Default")
      (node (ref "U1") (pin "J14") (pinfunction "RMII1_REF_CLK_J14") (pintype "bidirectional"))
    )
    (net (code "182") (name "unconnected-(U1F-CAP_VDD_RTC-PadD5)") (class "Default")
      (node (ref "U1") (pin "D5") (pinfunction "CAP_VDD_RTC_D5") (pintype "bidirectional"))
    )
    (net (code "183") (name "unconnected-(U1F-NC-PadD12)") (class "Default")
      (node (ref "U1") (pin "D12") (pinfunction "NC_D12") (pintype "bidirectional"))
    )
    (net (code "184") (name "unconnected-(U1F-NC-PadJ6)") (class "Default")
      (node (ref "U1") (pin "J6") (pinfunction "NC_J6") (pintype "bidirectional"))
    )
    (net (code "185") (name "unconnected-(U1F-NC-PadK4)") (class "Default")
      (node (ref "U1") (pin "K4") (pinfunction "NC_K4") (pintype "bidirectional"))
    )
    (net (code "186") (name "unconnected-(U1F-VPP-PadH6)") (class "Default")
      (node (ref "U1") (pin "H6") (pinfunction "VPP_H6") (pintype "bidirectional"))
    )
    (net (code "187") (name "unconnected-(U3-NC-Pad5)") (class "Default")
      (node (ref "U3") (pin "5") (pinfunction "NC_5") (pintype "bidirectional"))
    )
  )
)
